# GasSense.net
KiCad netlist of a schematic drawn in EAGLE
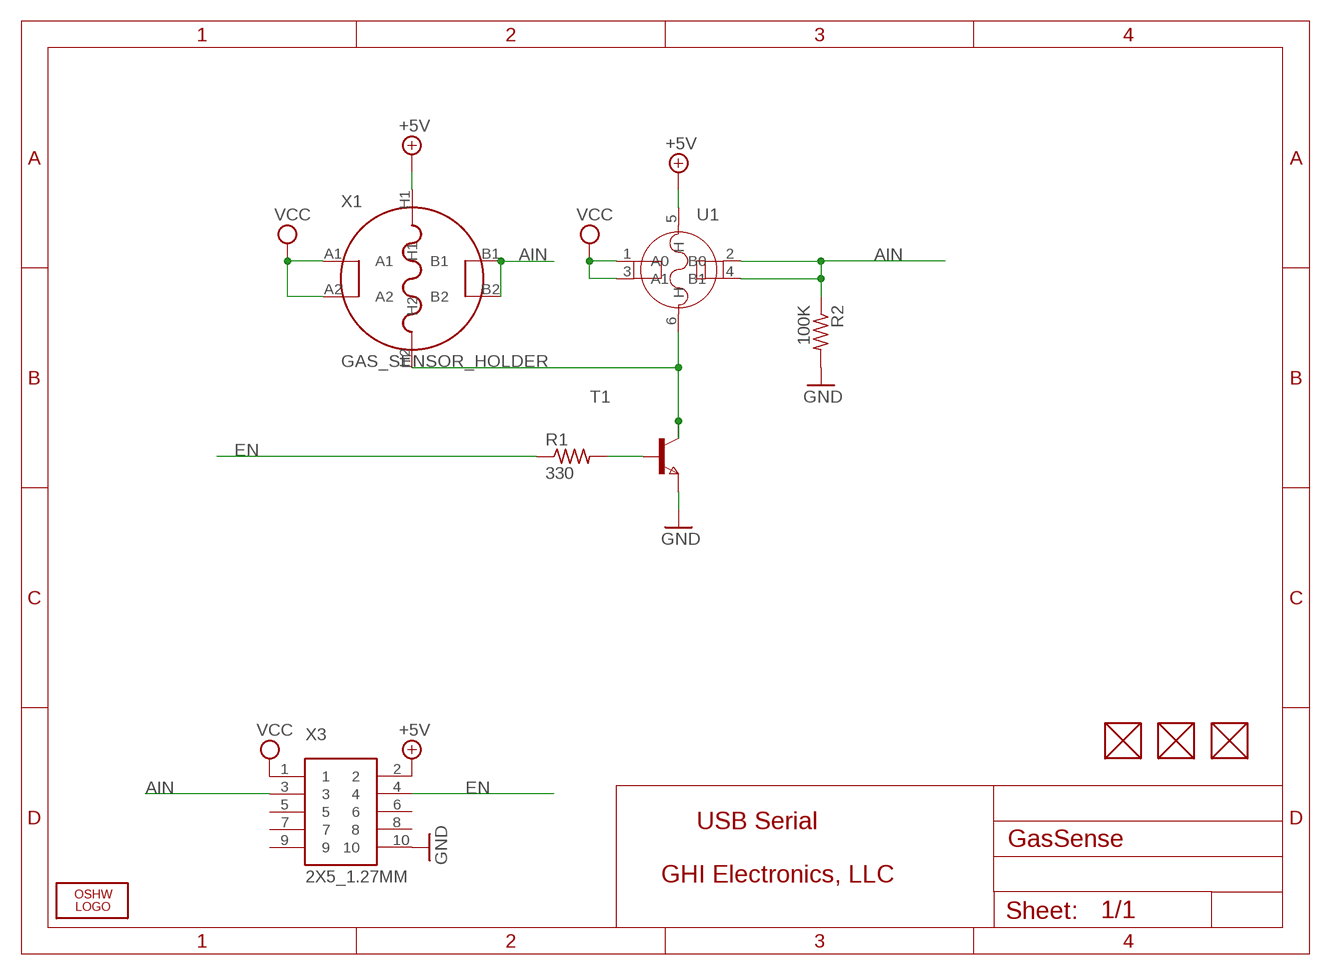
[diagram p0: schematic, sheet 1]

(export (version "E")
  (design (tool "Eeschema 10.0.6"))
  (components
    (comp (ref "FUD1")
      (value "FIDUCIAL")
      (footprint "eagle-import:FIDUCIAL_40MIL")
      (libsource (lib "eagle-import") (part "FIDUCIAL"))
    )
    (comp (ref "FUD2")
      (value "FIDUCIAL")
      (footprint "eagle-import:FIDUCIAL_40MIL")
      (libsource (lib "eagle-import") (part "FIDUCIAL"))
    )
    (comp (ref "FUD3")
      (value "FIDUCIAL")
      (footprint "eagle-import:FIDUCIAL_40MIL")
      (libsource (lib "eagle-import") (part "FIDUCIAL"))
    )
    (comp (ref "LOGO1")
      (value "LOGO-OSHW-FILLX0200-NT")
      (footprint "eagle-import:OSHW_FILLX200_NOTEXT")
      (libsource (lib "eagle-import") (part "LOGO-OSHW-FILLX0200-NT"))
    )
    (comp (ref "R1")
      (value "330")
      (footprint "eagle-import:R0603")
      (libsource (lib "eagle-import") (part "R-US_R0603"))
    )
    (comp (ref "R2")
      (value "100K")
      (footprint "eagle-import:R0603")
      (libsource (lib "eagle-import") (part "R-US_R0603"))
    )
    (comp (ref "T1")
      (value "NPNSOT223")
      (footprint "eagle-import:SOT223")
      (libsource (lib "eagle-import") (part "NPNSOT223"))
    )
    (comp (ref "U1")
      (value "SENSOR-MQ-5")
      (footprint "eagle-import:6P-LEADED-ROUND-D19")
      (libsource (lib "eagle-import") (part "SENSOR-MQ-5"))
    )
    (comp (ref "X1")
      (value "GAS_SENSOR_HOLDER")
      (footprint "eagle-import:GAS_SENSOR_HOLDER")
      (libsource (lib "eagle-import") (part "GAS_SENSOR_HOLDER"))
    )
    (comp (ref "X3")
      (value "2X5_1.27MM")
      (footprint "eagle-import:2X5_1.27MM")
      (libsource (lib "eagle-import") (part "2X5_1.27MM"))
    )
  )
  (nets
    (net (code "1") (name "+5V") (class "Default")
      (node (ref "U1") (pin "5") (pinfunction "H_5") (pintype "bidirectional"))
      (node (ref "X1") (pin "H1") (pinfunction "H1_H1") (pintype "bidirectional"))
      (node (ref "X3") (pin "2") (pinfunction "2_2") (pintype "bidirectional"))
    )
    (net (code "2") (name "/AIN") (class "Default")
      (node (ref "R2") (pin "1") (pinfunction "1_1") (pintype "passive"))
      (node (ref "U1") (pin "2") (pinfunction "B0_2") (pintype "bidirectional"))
      (node (ref "U1") (pin "4") (pinfunction "B1_4") (pintype "bidirectional"))
      (node (ref "X1") (pin "B1") (pinfunction "B1_B1") (pintype "bidirectional"))
      (node (ref "X1") (pin "B2") (pinfunction "B2_B2") (pintype "bidirectional"))
      (node (ref "X3") (pin "3") (pinfunction "3_3") (pintype "bidirectional"))
    )
    (net (code "3") (name "/EN") (class "Default")
      (node (ref "R1") (pin "1") (pinfunction "1_1") (pintype "passive"))
      (node (ref "X3") (pin "4") (pinfunction "4_4") (pintype "bidirectional"))
    )
    (net (code "4") (name "GND") (class "Default")
      (node (ref "R2") (pin "2") (pinfunction "2_2") (pintype "passive"))
      (node (ref "T1") (pin "3") (pinfunction "E_3") (pintype "passive"))
      (node (ref "X3") (pin "10") (pinfunction "10_10") (pintype "bidirectional"))
    )
    (net (code "5") (name "Net-(T1-B)") (class "Default")
      (node (ref "R1") (pin "2") (pinfunction "2_2") (pintype "passive"))
      (node (ref "T1") (pin "1") (pinfunction "B_1") (pintype "passive"))
    )
    (net (code "6") (name "Net-(T1-C1)") (class "Default")
      (node (ref "T1") (pin "2") (pinfunction "C1_2") (pintype "passive"))
      (node (ref "T1") (pin "4") (pinfunction "C2_4") (pintype "passive"))
      (node (ref "U1") (pin "6") (pinfunction "H_6") (pintype "bidirectional"))
      (node (ref "X1") (pin "H2") (pinfunction "H2_H2") (pintype "bidirectional"))
    )
    (net (code "7") (name "VCC") (class "Default")
      (node (ref "U1") (pin "1") (pinfunction "A0_1") (pintype "bidirectional"))
      (node (ref "U1") (pin "3") (pinfunction "A1_3") (pintype "bidirectional"))
      (node (ref "X1") (pin "A1") (pinfunction "A1_A1") (pintype "bidirectional"))
      (node (ref "X1") (pin "A2") (pinfunction "A2_A2") (pintype "bidirectional"))
      (node (ref "X3") (pin "1") (pinfunction "1_1") (pintype "bidirectional"))
    )
    (net (code "8") (name "unconnected-(FUD1-PadP$1)") (class "Default")
      (node (ref "FUD1") (pin "P$1") (pinfunction "P$1_P$1") (pintype "no_connect"))
    )
    (net (code "9") (name "unconnected-(FUD2-PadP$1)") (class "Default")
      (node (ref "FUD2") (pin "P$1") (pinfunction "P$1_P$1") (pintype "no_connect"))
    )
    (net (code "10") (name "unconnected-(FUD3-PadP$1)") (class "Default")
      (node (ref "FUD3") (pin "P$1") (pinfunction "P$1_P$1") (pintype "no_connect"))
    )
    (net (code "11") (name "unconnected-(X3-Pad5)") (class "Default")
      (node (ref "X3") (pin "5") (pinfunction "5_5") (pintype "bidirectional"))
    )
    (net (code "12") (name "unconnected-(X3-Pad6)") (class "Default")
      (node (ref "X3") (pin "6") (pinfunction "6_6") (pintype "bidirectional"))
    )
    (net (code "13") (name "unconnected-(X3-Pad7)") (class "Default")
      (node (ref "X3") (pin "7") (pinfunction "7_7") (pintype "bidirectional"))
    )
    (net (code "14") (name "unconnected-(X3-Pad8)") (class "Default")
      (node (ref "X3") (pin "8") (pinfunction "8_8") (pintype "bidirectional"))
    )
    (net (code "15") (name "unconnected-(X3-Pad9)") (class "Default")
      (node (ref "X3") (pin "9") (pinfunction "9_9") (pintype "bidirectional"))
    )
  )
)
